# SheetMicrocontroller.net
KiCad netlist of a schematic drawn in Altium Designer
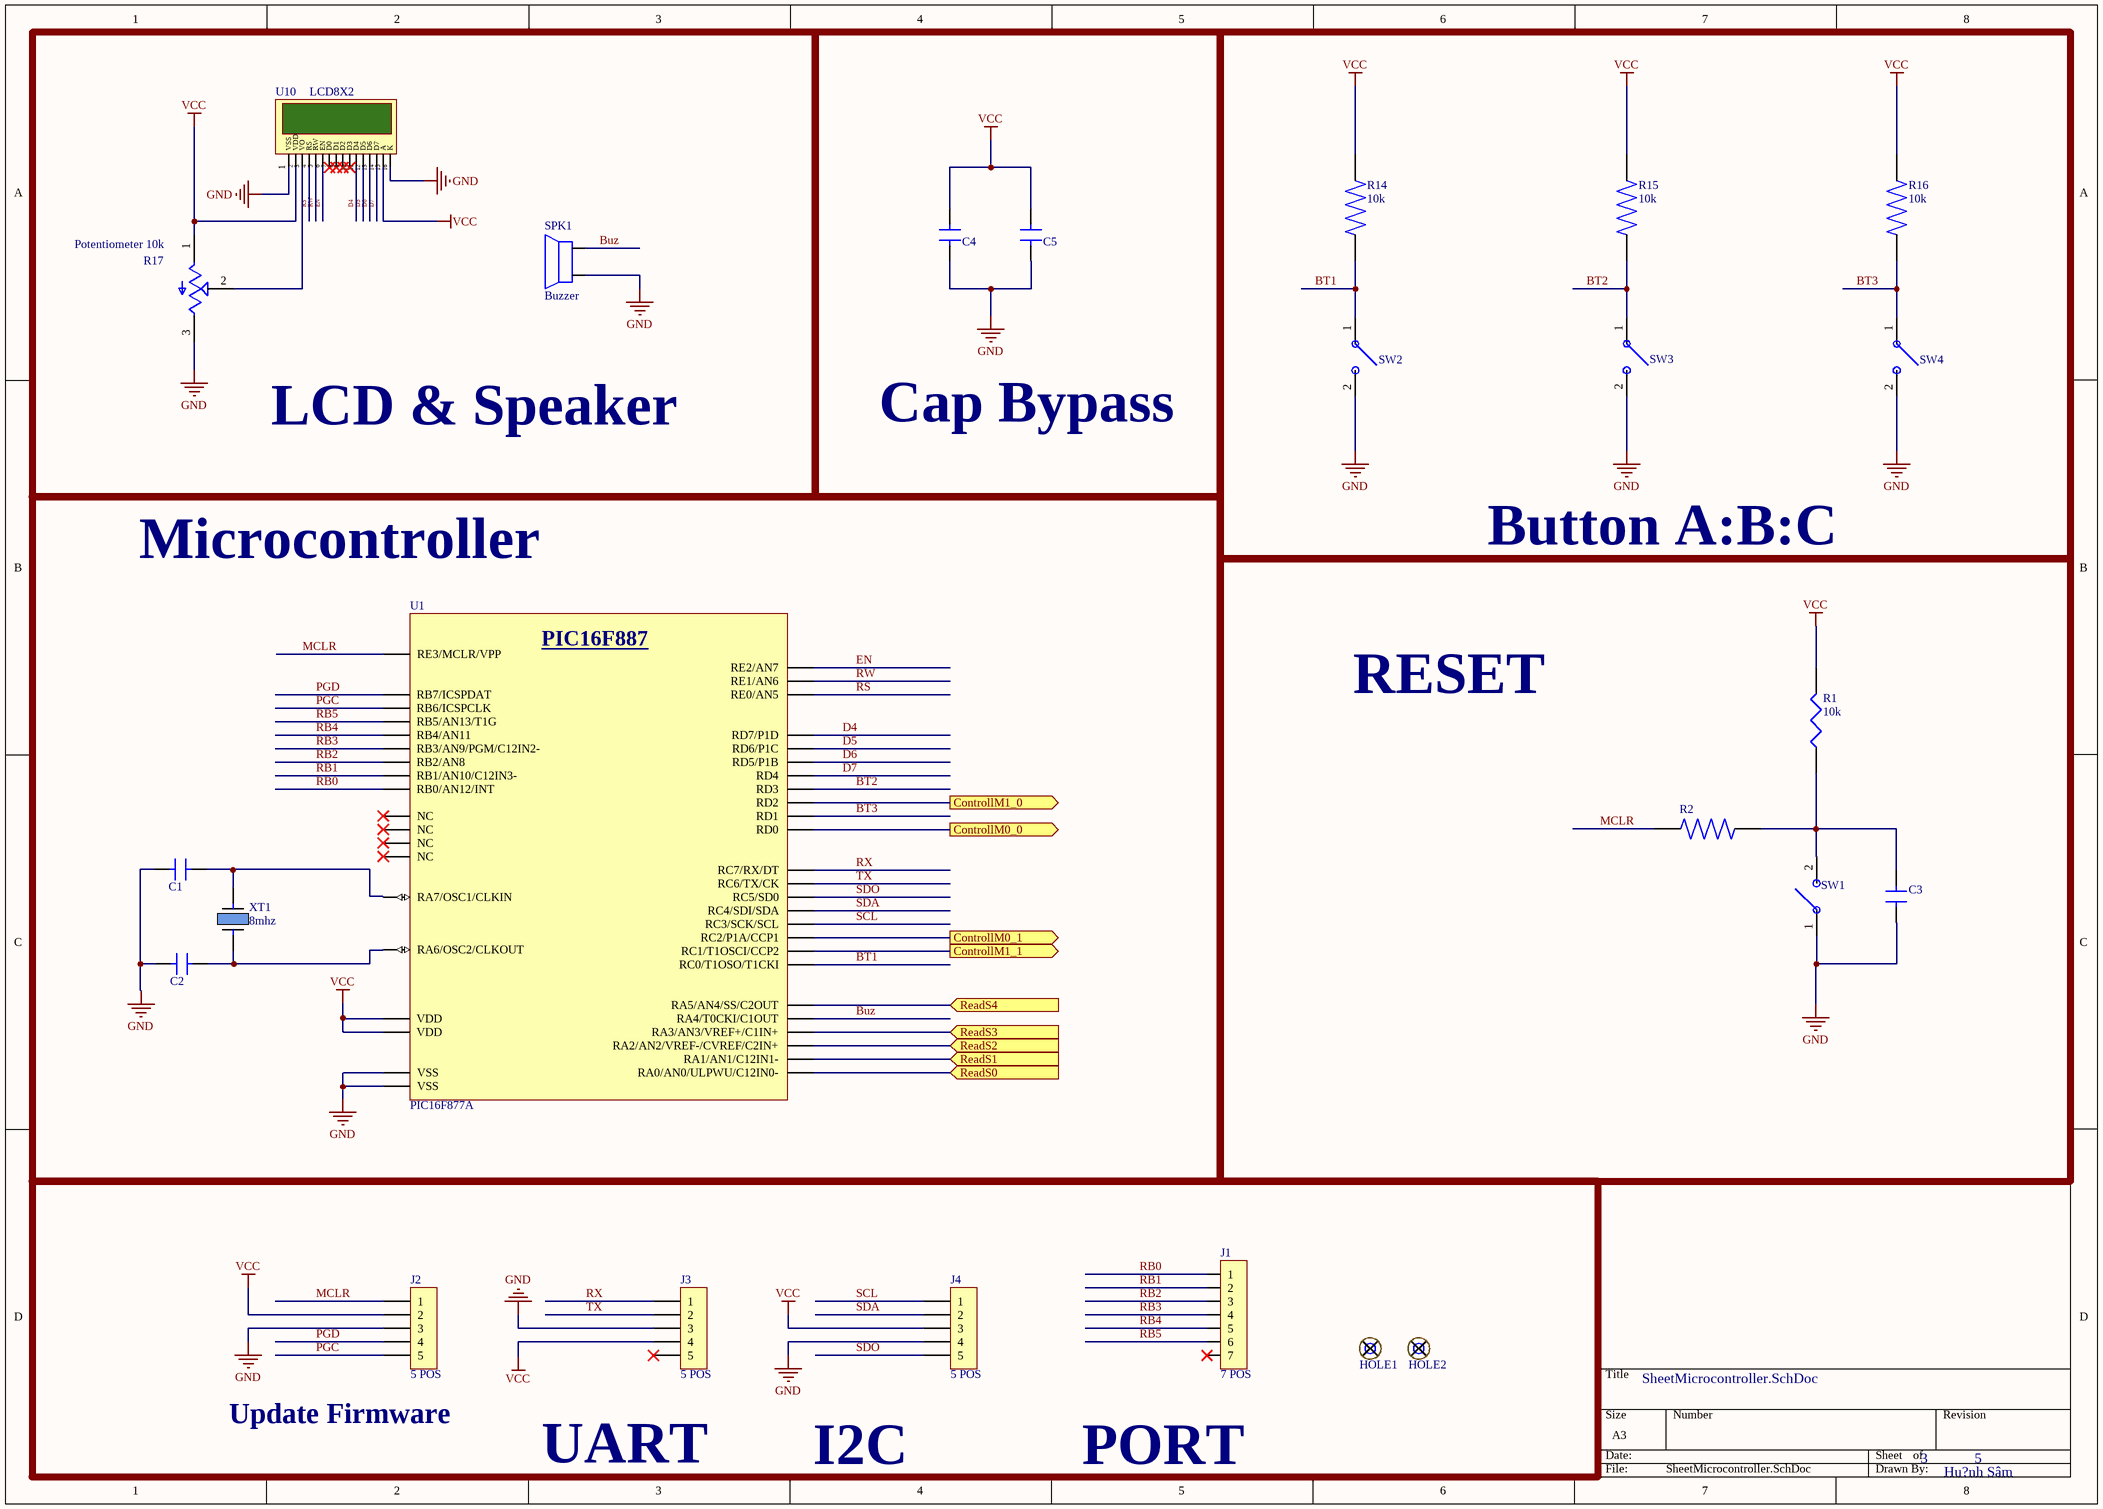
[diagram p0: SheetMicrocontroller.SchDoc]

(export (version "E")
  (design (tool "Eeschema 10.0.6"))
  (components
    (comp (ref "C1")
      (value "30PF 50V")
      (footprint "C0805 30PF 50V")
      (fields
        (field (name "MANUFACTURER") "KEMET")
        (field (name "MANUFACTURER PART NUMBER") "C0805X300J5GAC7800")
      )
      (libsource (lib "SchlibRobotLine") (part "C0805X300J5GAC7800"))
    )
    (comp (ref "C2")
      (value "30PF 50V")
      (footprint "C0805 30PF 50V")
      (fields
        (field (name "MANUFACTURER") "KEMET")
        (field (name "MANUFACTURER PART NUMBER") "C0805X300J5GAC7800")
      )
      (libsource (lib "SchlibRobotLine") (part "C0805X300J5GAC7800"))
    )
    (comp (ref "C3")
      (value "C0805C104K5RACTU")
      (footprint "CAP104 0.1UF 50V")
      (description "Cap Ceramic 0.1uF 50V X7R 10% SMD 2.0 x 1.2 mm 125 C Paper T/R")
      (fields (field (name "MANUFACTURER") "KEMET") (field (name "TOLERANCE") "10%"))
      (libsource (lib "SchlibRobotLine") (part "C0805C104K5RACTU"))
    )
    (comp (ref "C4")
      (value "C0805C104K5RACTU")
      (footprint "CAP104 0.1UF 50V")
      (description "Cap Ceramic 0.1uF 50V X7R 10% SMD 2.0 x 1.2 mm 125 C Paper T/R")
      (fields (field (name "MANUFACTURER") "KEMET") (field (name "TOLERANCE") "10%"))
      (libsource (lib "SchlibRobotLine") (part "C0805C104K5RACTU"))
    )
    (comp (ref "C5")
      (value "C0805C104K5RACTU")
      (footprint "CAP104 0.1UF 50V")
      (description "Cap Ceramic 0.1uF 50V X7R 10% SMD 2.0 x 1.2 mm 125 C Paper T/R")
      (fields (field (name "MANUFACTURER") "KEMET") (field (name "TOLERANCE") "10%"))
      (libsource (lib "SchlibRobotLine") (part "C0805C104K5RACTU"))
    )
    (comp (ref "HOLE1")
      (value "Hole")
      (footprint "Hole 2MM")
      (description "Hole 3mm")
      (libsource (lib "SchlibRobotLine") (part "Hole 2mm"))
    )
    (comp (ref "HOLE2")
      (value "Hole")
      (footprint "Hole 2MM")
      (description "Hole 3mm")
      (libsource (lib "SchlibRobotLine") (part "Hole 2mm"))
    )
    (comp (ref "J1")
      (value "7 POS")
      (footprint "CONN HEADER VERT 7POS 2.54MM")
      (description "Header Connector, Pcb Mount, Recept, 7 Contacts, Pin, 0.1 Pitch, Pc Tail Terminal")
      (fields (field (name "MANUFACTURER") "Molex") (field (name "MANUFACTURER PART NUMBER") "0022284074"))
      (libsource (lib "SchlibRobotLine") (part "0022284074"))
    )
    (comp (ref "J2")
      (value "5 POS")
      (footprint "CONN HEADER VERT 5POS 2.54MM")
      (description "Conn Header Vert 5POS 2.54MM")
      (fields
        (field (name "MANUFACTURER") "Sullins")
        (field (name "MANUFACTURER PART NUMBER") "PRPC005SACN-RC")
      )
      (libsource (lib "SchlibRobotLine") (part "PRPC005SACN-RC"))
    )
    (comp (ref "J3")
      (value "5 POS")
      (footprint "CONN HEADER VERT 5POS 2.54MM")
      (description "Conn Header Vert 5POS 2.54MM")
      (fields
        (field (name "MANUFACTURER") "Sullins")
        (field (name "MANUFACTURER PART NUMBER") "PRPC005SACN-RC")
      )
      (libsource (lib "SchlibRobotLine") (part "PRPC005SACN-RC"))
    )
    (comp (ref "J4")
      (value "5 POS")
      (footprint "CONN HEADER VERT 5POS 2.54MM")
      (description "Conn Header Vert 5POS 2.54MM")
      (fields
        (field (name "MANUFACTURER") "Sullins")
        (field (name "MANUFACTURER PART NUMBER") "PRPC005SACN-RC")
      )
      (libsource (lib "SchlibRobotLine") (part "PRPC005SACN-RC"))
    )
    (comp (ref "R1")
      (value "10k")
      (footprint "RC0805 10K OHM 1% 1/8W")
      (description "RES SMD 10K OHM 1% 1/8W 0805")
      (fields
        (field (name "MANUFACTURER") "Yageo")
        (field (name "MANUFACTURER PART NUMBER") "RC0805FR-0710KL")
      )
      (libsource (lib "") (part "RC0805FR-0710KL_1"))
    )
    (comp (ref "R2")
      (value "RC0805JR-07470RL")
      (footprint "RC0805JR-07470RL")
      (description "RES SMD 470 OHM 5% 1/8W 0805")
      (fields (field (name "MANUFACTURER") "Yageo Phycomp") (field (name "TOLERANCE") "5%"))
      (libsource (lib "SchlibRobotLine") (part "RC0805JR-07470RL"))
    )
    (comp (ref "R14")
      (value "10k")
      (footprint "RC0805 10K OHM 1% 1/8W")
      (description "RES SMD 10K OHM 1% 1/8W 0805")
      (fields
        (field (name "MANUFACTURER") "Yageo")
        (field (name "MANUFACTURER PART NUMBER") "RC0805FR-0710KL")
      )
      (libsource (lib "SchlibRobotLine") (part "RC0805FR-0710KL"))
    )
    (comp (ref "R15")
      (value "10k")
      (footprint "RC0805 10K OHM 1% 1/8W")
      (description "RES SMD 10K OHM 1% 1/8W 0805")
      (fields
        (field (name "MANUFACTURER") "Yageo")
        (field (name "MANUFACTURER PART NUMBER") "RC0805FR-0710KL")
      )
      (libsource (lib "SchlibRobotLine") (part "RC0805FR-0710KL"))
    )
    (comp (ref "R16")
      (value "10k")
      (footprint "RC0805 10K OHM 1% 1/8W")
      (description "RES SMD 10K OHM 1% 1/8W 0805")
      (fields
        (field (name "MANUFACTURER") "Yageo")
        (field (name "MANUFACTURER PART NUMBER") "RC0805FR-0710KL")
      )
      (libsource (lib "SchlibRobotLine") (part "RC0805FR-0710KL"))
    )
    (comp (ref "R17")
      (value "Potentiometer 10k")
      (footprint "TRIM_TC33X-2-103E")
      (description "10 kOhms 0.1W, 1/10W J Lead Surface Mount Trimmer Potentiometer Cermet 1 Turn Top Adjustment")
      (fields (field (name "MP") "TC33X-2-103E") (field (name "MF") "Bourns"))
      (libsource (lib "SchlibRobotLine") (part "TC33X-2-103E"))
    )
    (comp (ref "SPK1")
      (value "Buzzer")
      (footprint "BUZZER")
      (description "AUDIO MAGNETIC XDCR 3-7V TH")
      (fields
        (field (name "MANUFACTURER") "Projects Unlimited")
        (field (name "MANUFACTURER PART NUMBER") "AT-1224-TWT-5V-2-R")
      )
      (libsource (lib "SchlibRobotLine") (part "AT-1224-TWT-5V-2-R"))
    )
    (comp (ref "SW1")
      (value "PTS636SM43JSMTRLFS")
      (footprint "PTS636 SM43J SMTR LFS")
      (description "Switch Reset")
      (fields (field (name "MANUFACTURER") "ITT C&K"))
      (libsource (lib "SchlibRobotLine") (part "PTS636SM43JSMTRLFS"))
    )
    (comp (ref "SW2")
      (value "PTS636SM43JSMTRLFS")
      (footprint "PTS636 SM43J SMTR LFS")
      (description "Switch Reset")
      (fields (field (name "MANUFACTURER") "ITT C&K"))
      (libsource (lib "SchlibRobotLine") (part "PTS636SM43JSMTRLFS"))
    )
    (comp (ref "SW3")
      (value "PTS636SM43JSMTRLFS")
      (footprint "PTS636 SM43J SMTR LFS")
      (description "Switch Reset")
      (fields (field (name "MANUFACTURER") "ITT C&K"))
      (libsource (lib "SchlibRobotLine") (part "PTS636SM43JSMTRLFS"))
    )
    (comp (ref "SW4")
      (value "PTS636SM43JSMTRLFS")
      (footprint "PTS636 SM43J SMTR LFS")
      (description "Switch Reset")
      (fields (field (name "MANUFACTURER") "ITT C&K"))
      (libsource (lib "SchlibRobotLine") (part "PTS636SM43JSMTRLFS"))
    )
    (comp (ref "U1")
      (value "PIC16F877A")
      (footprint "TQFP80P1200X1200X120-44N")
      (fields
        (field (name "MANUFACTURER") "Microchip")
        (field (name "MANUFACTURER PART NUMBER") "PIC16F887-I/PT")
      )
      (libsource (lib "SchlibRobotLine") (part "PIC16F887-I/PT"))
    )
    (comp (ref "U10")
      (value "LCD8X2")
      (footprint "LCD0802")
      (description "LCD ALPHA/NUM DISPL 8X2 YW/GN BK")
      (fields
        (field (name "MANUFACTURER") "Matrix Orbital")
        (field (name "MANUFACTURER PART NUMBER") "LCD0821")
      )
      (libsource (lib "SchlibRobotLine") (part "LCD0821"))
    )
    (comp (ref "XT1")
      (value "8mhz")
      (footprint "CAPAE13348X42M")
      (description "ABRACON         ABLS-8.000MHZ-K4T             CRYSTAL, 8MHZ, 18PF, HC-49US")
      (fields
        (field (name "MANUFACTURER") "Abracon")
        (field (name "MANUFACTURER PART NUMBER") "ABLS-8.000MHZ-K4T")
      )
      (libsource (lib "SchlibRobotLine") (part "ABLS-8.000MHZ-K4T"))
    )
  )
  (nets
    (net (code "1") (name "/BT1") (class "Default")
      (node (ref "R14") (pin "1") (pinfunction "1_1") (pintype "passive"))
      (node (ref "SW2") (pin "1") (pinfunction "1_1") (pintype "passive"))
      (node (ref "U1") (pin "32") (pinfunction "RC0/T1OSO/T1CKI_32") (pintype "passive"))
    )
    (net (code "2") (name "/BT2") (class "Default")
      (node (ref "R15") (pin "1") (pinfunction "1_1") (pintype "passive"))
      (node (ref "SW3") (pin "1") (pinfunction "1_1") (pintype "passive"))
      (node (ref "U1") (pin "41") (pinfunction "RD3_41") (pintype "passive"))
    )
    (net (code "3") (name "/BT3") (class "Default")
      (node (ref "R16") (pin "1") (pinfunction "1_1") (pintype "passive"))
      (node (ref "SW4") (pin "1") (pinfunction "1_1") (pintype "passive"))
      (node (ref "U1") (pin "39") (pinfunction "RD1_39") (pintype "passive"))
    )
    (net (code "4") (name "/Buz") (class "Default")
      (node (ref "SPK1") (pin "1") (pinfunction "1_1") (pintype "passive"))
      (node (ref "U1") (pin "23") (pinfunction "RA4/T0CKI/C1OUT_23") (pintype "passive"))
    )
    (net (code "5") (name "/ControllM0_0") (class "Default")
      (node (ref "U1") (pin "38") (pinfunction "RD0_38") (pintype "passive"))
    )
    (net (code "6") (name "/ControllM0_1") (class "Default")
      (node (ref "U1") (pin "36") (pinfunction "RC2/P1A/CCP1_36") (pintype "passive"))
    )
    (net (code "7") (name "/ControllM1_0") (class "Default")
      (node (ref "U1") (pin "40") (pinfunction "RD2_40") (pintype "passive"))
    )
    (net (code "8") (name "/ControllM1_1") (class "Default")
      (node (ref "U1") (pin "35") (pinfunction "RC1/T1OSCI/CCP2_35") (pintype "passive"))
    )
    (net (code "9") (name "/D4") (class "Default")
      (node (ref "U1") (pin "5") (pinfunction "RD7/P1D_5") (pintype "passive"))
      (node (ref "U10") (pin "11") (pinfunction "D4_11") (pintype "passive"))
    )
    (net (code "10") (name "/D5") (class "Default")
      (node (ref "U1") (pin "4") (pinfunction "RD6/P1C_4") (pintype "passive"))
      (node (ref "U10") (pin "12") (pinfunction "D5_12") (pintype "passive"))
    )
    (net (code "11") (name "/D6") (class "Default")
      (node (ref "U1") (pin "3") (pinfunction "RD5/P1B_3") (pintype "passive"))
      (node (ref "U10") (pin "13") (pinfunction "D6_13") (pintype "passive"))
    )
    (net (code "12") (name "/D7") (class "Default")
      (node (ref "U1") (pin "2") (pinfunction "RD4_2") (pintype "passive"))
      (node (ref "U10") (pin "14") (pinfunction "D7_14") (pintype "passive"))
    )
    (net (code "13") (name "/EN") (class "Default")
      (node (ref "U1") (pin "27") (pinfunction "RE2/AN7_27") (pintype "passive"))
      (node (ref "U10") (pin "6") (pinfunction "EN_6") (pintype "passive"))
    )
    (net (code "14") (name "/MCLR") (class "Default")
      (node (ref "J2") (pin "1") (pinfunction "1_1") (pintype "passive"))
      (node (ref "R2") (pin "1") (pinfunction "1_1") (pintype "passive"))
      (node (ref "U1") (pin "18") (pinfunction "RE3/MCLR/VPP_18") (pintype "passive"))
    )
    (net (code "15") (name "/PGC") (class "Default")
      (node (ref "J2") (pin "5") (pinfunction "5_5") (pintype "passive"))
      (node (ref "U1") (pin "16") (pinfunction "RB6/ICSPCLK_16") (pintype "passive"))
    )
    (net (code "16") (name "/PGD") (class "Default")
      (node (ref "J2") (pin "4") (pinfunction "4_4") (pintype "passive"))
      (node (ref "U1") (pin "17") (pinfunction "RB7/ICSPDAT_17") (pintype "passive"))
    )
    (net (code "17") (name "/RB0") (class "Default")
      (node (ref "J1") (pin "1") (pinfunction "1_1") (pintype "passive"))
      (node (ref "U1") (pin "8") (pinfunction "RB0/AN12/INT_8") (pintype "passive"))
    )
    (net (code "18") (name "/RB1") (class "Default")
      (node (ref "J1") (pin "2") (pinfunction "2_2") (pintype "passive"))
      (node (ref "U1") (pin "9") (pinfunction "RB1/AN10/C12IN3-_9") (pintype "passive"))
    )
    (net (code "19") (name "/RB2") (class "Default")
      (node (ref "J1") (pin "3") (pinfunction "3_3") (pintype "passive"))
      (node (ref "U1") (pin "10") (pinfunction "RB2/AN8_10") (pintype "passive"))
    )
    (net (code "20") (name "/RB3") (class "Default")
      (node (ref "J1") (pin "4") (pinfunction "4_4") (pintype "passive"))
      (node (ref "U1") (pin "11") (pinfunction "RB3/AN9/PGM/C12IN2-_11") (pintype "passive"))
    )
    (net (code "21") (name "/RB4") (class "Default")
      (node (ref "J1") (pin "5") (pinfunction "5_5") (pintype "passive"))
      (node (ref "U1") (pin "14") (pinfunction "RB4/AN11_14") (pintype "passive"))
    )
    (net (code "22") (name "/RB5") (class "Default")
      (node (ref "J1") (pin "6") (pinfunction "6_6") (pintype "passive"))
      (node (ref "U1") (pin "15") (pinfunction "RB5/AN13/T1G_15") (pintype "passive"))
    )
    (net (code "23") (name "/RS") (class "Default")
      (node (ref "U1") (pin "25") (pinfunction "RE0/AN5_25") (pintype "passive"))
      (node (ref "U10") (pin "4") (pinfunction "RS_4") (pintype "passive"))
    )
    (net (code "24") (name "/RW") (class "Default")
      (node (ref "U1") (pin "26") (pinfunction "RE1/AN6_26") (pintype "passive"))
      (node (ref "U10") (pin "5") (pinfunction "RW_5") (pintype "passive"))
    )
    (net (code "25") (name "/RX") (class "Default")
      (node (ref "J3") (pin "1") (pinfunction "1_1") (pintype "passive"))
      (node (ref "U1") (pin "1") (pinfunction "RC7/RX/DT_1") (pintype "passive"))
    )
    (net (code "26") (name "/ReadS0") (class "Default")
      (node (ref "U1") (pin "19") (pinfunction "RA0/AN0/ULPWU/C12IN0-_19") (pintype "passive"))
    )
    (net (code "27") (name "/ReadS1") (class "Default")
      (node (ref "U1") (pin "20") (pinfunction "RA1/AN1/C12IN1-_20") (pintype "passive"))
    )
    (net (code "28") (name "/ReadS2") (class "Default")
      (node (ref "U1") (pin "21") (pinfunction "RA2/AN2/VREF-/CVREF/C2IN+_21") (pintype "passive"))
    )
    (net (code "29") (name "/ReadS3") (class "Default")
      (node (ref "U1") (pin "22") (pinfunction "RA3/AN3/VREF+/C1IN+_22") (pintype "passive"))
    )
    (net (code "30") (name "/ReadS4") (class "Default")
      (node (ref "U1") (pin "24") (pinfunction "RA5/AN4/SS/C2OUT_24") (pintype "passive"))
    )
    (net (code "31") (name "/SCL") (class "Default")
      (node (ref "J4") (pin "1") (pinfunction "1_1") (pintype "passive"))
      (node (ref "U1") (pin "37") (pinfunction "RC3/SCK/SCL_37") (pintype "passive"))
    )
    (net (code "32") (name "/SDA") (class "Default")
      (node (ref "J4") (pin "2") (pinfunction "2_2") (pintype "passive"))
      (node (ref "U1") (pin "42") (pinfunction "RC4/SDI/SDA_42") (pintype "passive"))
    )
    (net (code "33") (name "/SDO") (class "Default")
      (node (ref "J4") (pin "5") (pinfunction "5_5") (pintype "passive"))
      (node (ref "U1") (pin "43") (pinfunction "RC5/SD0_43") (pintype "passive"))
    )
    (net (code "34") (name "/TX") (class "Default")
      (node (ref "J3") (pin "2") (pinfunction "2_2") (pintype "passive"))
      (node (ref "U1") (pin "44") (pinfunction "RC6/TX/CK_44") (pintype "passive"))
    )
    (net (code "35") (name "GND") (class "Default")
      (node (ref "C1") (pin "1") (pinfunction "1_1") (pintype "passive"))
      (node (ref "C2") (pin "1") (pinfunction "1_1") (pintype "passive"))
      (node (ref "C3") (pin "1") (pinfunction "1_1") (pintype "passive"))
      (node (ref "C4") (pin "1") (pinfunction "1_1") (pintype "passive"))
      (node (ref "C5") (pin "1") (pinfunction "1_1") (pintype "passive"))
      (node (ref "J2") (pin "3") (pinfunction "3_3") (pintype "passive"))
      (node (ref "J3") (pin "3") (pinfunction "3_3") (pintype "passive"))
      (node (ref "J4") (pin "4") (pinfunction "4_4") (pintype "passive"))
      (node (ref "R17") (pin "3") (pinfunction "CW_3") (pintype "passive"))
      (node (ref "SPK1") (pin "2") (pinfunction "2_2") (pintype "passive"))
      (node (ref "SW1") (pin "1") (pinfunction "1_1") (pintype "passive"))
      (node (ref "SW2") (pin "2") (pinfunction "2_2") (pintype "passive"))
      (node (ref "SW3") (pin "2") (pinfunction "2_2") (pintype "passive"))
      (node (ref "SW4") (pin "2") (pinfunction "2_2") (pintype "passive"))
      (node (ref "U1") (pin "29") (pinfunction "VSS_29") (pintype "power_in"))
      (node (ref "U1") (pin "6") (pinfunction "VSS_6") (pintype "power_in"))
      (node (ref "U10") (pin "1") (pinfunction "VSS_1") (pintype "passive"))
      (node (ref "U10") (pin "16") (pinfunction "K_16") (pintype "passive"))
    )
    (net (code "36") (name "Net-(C3-Pad2)") (class "Default")
      (node (ref "C3") (pin "2") (pinfunction "2_2") (pintype "passive"))
      (node (ref "R1") (pin "1") (pinfunction "1_1") (pintype "passive"))
      (node (ref "R2") (pin "2") (pinfunction "2_2") (pintype "passive"))
      (node (ref "SW1") (pin "2") (pinfunction "2_2") (pintype "passive"))
    )
    (net (code "37") (name "Net-(R17-W)") (class "Default")
      (node (ref "R17") (pin "2") (pinfunction "W_2") (pintype "passive"))
      (node (ref "U10") (pin "3") (pinfunction "VO_3") (pintype "passive"))
    )
    (net (code "38") (name "Net-(U1-RA6{slash}OSC2{slash}CLKOUT)") (class "Default")
      (node (ref "C2") (pin "2") (pinfunction "2_2") (pintype "passive"))
      (node (ref "U1") (pin "31") (pinfunction "RA6/OSC2/CLKOUT_31") (pintype "bidirectional"))
      (node (ref "XT1") (pin "1") (pinfunction "1_1") (pintype "passive"))
    )
    (net (code "39") (name "Net-(U1-RA7{slash}OSC1{slash}CLKIN)") (class "Default")
      (node (ref "C1") (pin "2") (pinfunction "2_2") (pintype "passive"))
      (node (ref "U1") (pin "30") (pinfunction "RA7/OSC1/CLKIN_30") (pintype "bidirectional"))
      (node (ref "XT1") (pin "2") (pinfunction "2_2") (pintype "passive"))
    )
    (net (code "40") (name "VCC") (class "Default")
      (node (ref "C4") (pin "2") (pinfunction "2_2") (pintype "passive"))
      (node (ref "C5") (pin "2") (pinfunction "2_2") (pintype "passive"))
      (node (ref "J2") (pin "2") (pinfunction "2_2") (pintype "passive"))
      (node (ref "J3") (pin "4") (pinfunction "4_4") (pintype "passive"))
      (node (ref "J4") (pin "3") (pinfunction "3_3") (pintype "passive"))
      (node (ref "R1") (pin "2") (pinfunction "2_2") (pintype "passive"))
      (node (ref "R14") (pin "2") (pinfunction "2_2") (pintype "passive"))
      (node (ref "R15") (pin "2") (pinfunction "2_2") (pintype "passive"))
      (node (ref "R16") (pin "2") (pinfunction "2_2") (pintype "passive"))
      (node (ref "R17") (pin "1") (pinfunction "CCW_1") (pintype "passive"))
      (node (ref "U1") (pin "28") (pinfunction "VDD_28") (pintype "power_in"))
      (node (ref "U1") (pin "7") (pinfunction "VDD_7") (pintype "power_in"))
      (node (ref "U10") (pin "15") (pinfunction "A_15") (pintype "passive"))
      (node (ref "U10") (pin "2") (pinfunction "VDD_2") (pintype "passive"))
    )
    (net (code "41") (name "unconnected-(J1-Pad7)") (class "Default")
      (node (ref "J1") (pin "7") (pinfunction "7_7") (pintype "passive+no_connect"))
    )
    (net (code "42") (name "unconnected-(J3-Pad5)") (class "Default")
      (node (ref "J3") (pin "5") (pinfunction "5_5") (pintype "passive+no_connect"))
    )
    (net (code "43") (name "unconnected-(U1-NC-Pad12)") (class "Default")
      (node (ref "U1") (pin "12") (pinfunction "NC_12") (pintype "passive+no_connect"))
    )
    (net (code "44") (name "unconnected-(U1-NC-Pad13)") (class "Default")
      (node (ref "U1") (pin "13") (pinfunction "NC_13") (pintype "passive+no_connect"))
    )
    (net (code "45") (name "unconnected-(U1-NC-Pad33)") (class "Default")
      (node (ref "U1") (pin "33") (pinfunction "NC_33") (pintype "passive+no_connect"))
    )
    (net (code "46") (name "unconnected-(U1-NC-Pad34)") (class "Default")
      (node (ref "U1") (pin "34") (pinfunction "NC_34") (pintype "passive+no_connect"))
    )
    (net (code "47") (name "unconnected-(U10-D0-Pad7)") (class "Default")
      (node (ref "U10") (pin "7") (pinfunction "D0_7") (pintype "passive+no_connect"))
    )
    (net (code "48") (name "unconnected-(U10-D1-Pad8)") (class "Default")
      (node (ref "U10") (pin "8") (pinfunction "D1_8") (pintype "passive+no_connect"))
    )
    (net (code "49") (name "unconnected-(U10-D2-Pad9)") (class "Default")
      (node (ref "U10") (pin "9") (pinfunction "D2_9") (pintype "passive+no_connect"))
    )
    (net (code "50") (name "unconnected-(U10-D3-Pad10)") (class "Default")
      (node (ref "U10") (pin "10") (pinfunction "D3_10") (pintype "passive+no_connect"))
    )
  )
)
